# GNSS_A.net
KiCad netlist of a schematic drawn in Altium Designer
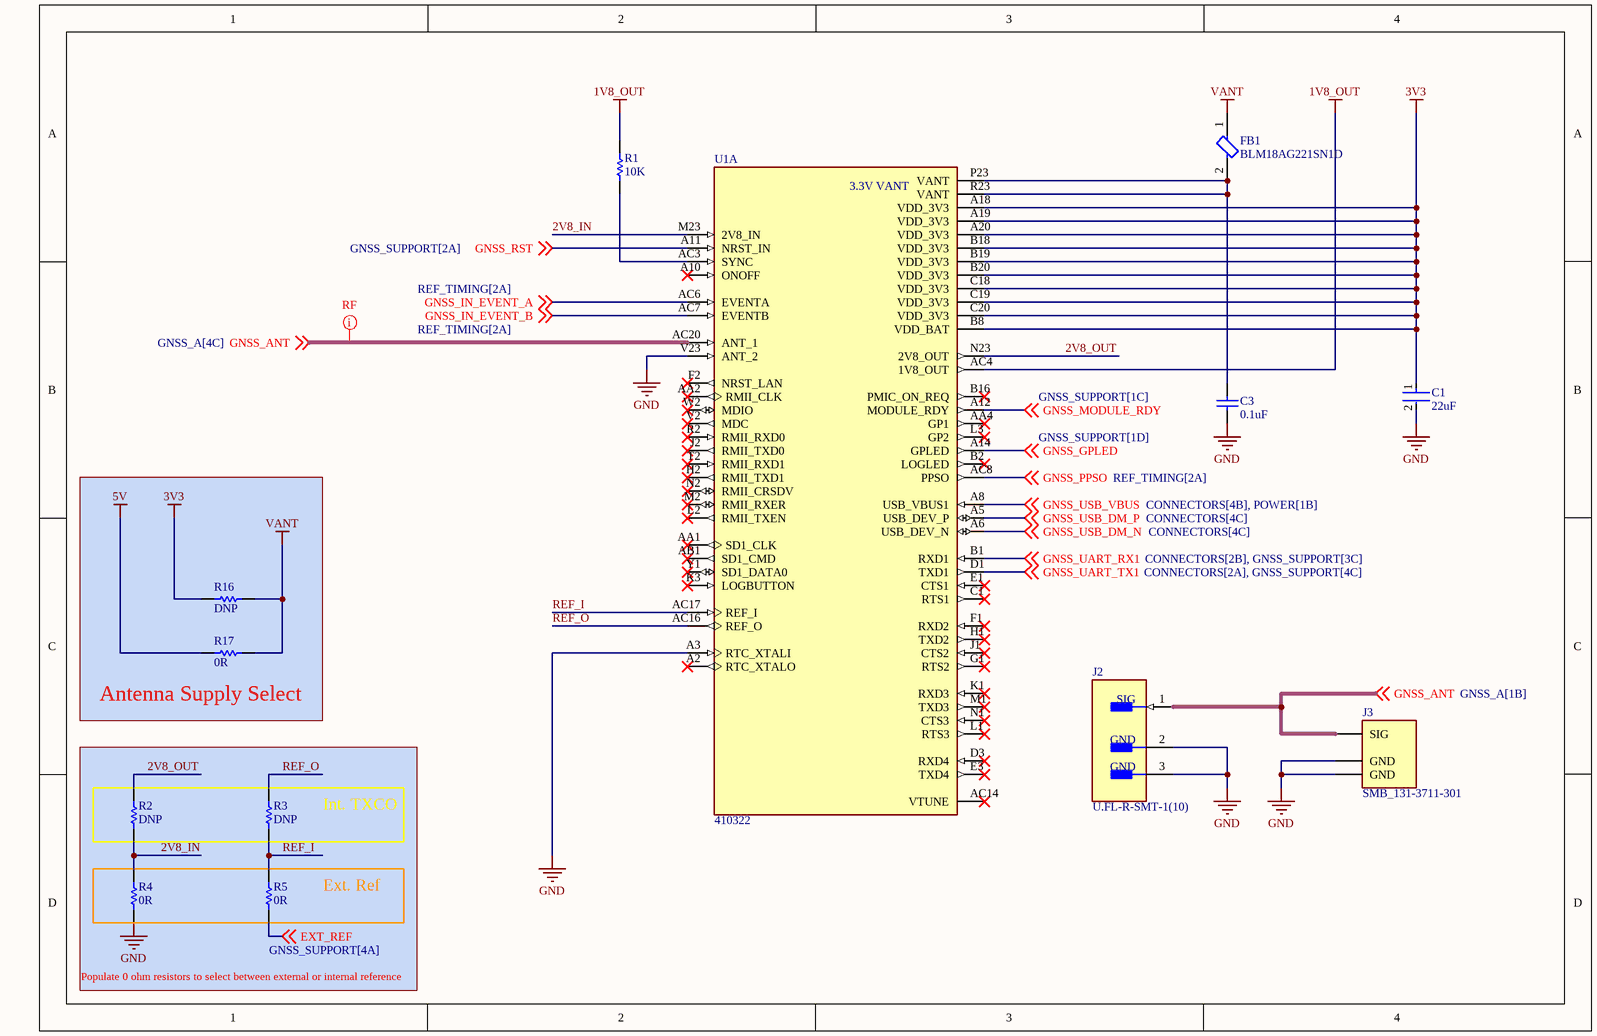
[diagram p0: GNSS_A.SchDoc]

(export (version "E")
  (design (tool "Eeschema 10.0.6"))
  (components
    (comp (ref "C1")
      (value "22uF")
      (footprint "FP-CL10-IPC_B")
      (description "Cap Ceramic 22uF 10V X5R ±20% Pad SMD 0603 +85°C T/R")
      (fields (field (name "TOLERANCE") "20%"))
      (libsource (lib "Altium Content Vault") (part "b4654b650e69147ec39a6b967a45e02"))
    )
    (comp (ref "C3")
      (value "0.1uF")
      (footprint "CAPC1005X56X25LL10T15")
      (fields
        (field (name "MANUFACTURER") "AVX Interconnect / Elco")
        (field (name "PART NUMBER") "04026D104KAT2A")
      )
      (libsource (lib "Altium Content Vault") (part "CAP"))
    )
    (comp (ref "FB1")
      (value "BLM18AG221SN1D")
      (footprint "FP-BLM18-0_15-t0_8-IPC_A")
      (description "Chip Ferrite Bead, 0603, 220Ω @ 100MHz, 0.25Ω, 25%, 700mA")
      (fields (field (name "TOLERANCE") "25%"))
      (libsource (lib "Altium Content Vault") (part "5f30dd21d616792df468990f7003faa"))
    )
    (comp (ref "J2")
      (value "U.FL-R-SMT-1(10)")
      (footprint "FP-U_FL-R-SMT-1_10-MFG")
      (description "CONN U.FL RCPT STR 50 OHM SMD")
      (libsource (lib "Altium Content Vault") (part "7158abf7d987fa84906f6fb0d115710"))
    )
    (comp (ref "J3")
      (value "SMB_131-3711-301")
      (footprint "SMB_131-3711-301")
      (description "Rf Coaxial Board Mount Connector")
      (fields
        (field (name "MANUFACTURER") "Bel Cinch")
        (field (name "MANUFACTURER PART NUMBER") "131-3711-301")
      )
      (libsource (lib "GNSS_Receiver_Library") (part "SMB_131-3711-301"))
    )
    (comp (ref "R1")
      (value "10K")
      (footprint "RESC1005X40X25LL05T10")
      (fields (field (name "PART NUMBER") "RC0402FR-0710KL") (field (name "MANUFACTURER") "Yageo / Phycomp"))
      (libsource (lib "Altium Content Vault") (part "RES"))
    )
    (comp (ref "R2")
      (value "DNP")
      (footprint "RESC1005X40X25NL05T10")
      (fields (field (name "MANUFACTURER") "Yageo / Phycomp") (field (name "PART NUMBER") "RC0402JR-070RL"))
      (libsource (lib "Altium Content Vault") (part "RES"))
    )
    (comp (ref "R3")
      (value "DNP")
      (footprint "RESC1005X40X25NL05T10")
      (fields (field (name "MANUFACTURER") "Yageo / Phycomp") (field (name "PART NUMBER") "RC0402JR-070RL"))
      (libsource (lib "Altium Content Vault") (part "RES"))
    )
    (comp (ref "R4")
      (value "0R")
      (footprint "RESC1005X40X25NL05T10")
      (fields (field (name "MANUFACTURER") "Yageo / Phycomp") (field (name "PART NUMBER") "RC0402JR-070RL"))
      (libsource (lib "Altium Content Vault") (part "RES"))
    )
    (comp (ref "R5")
      (value "0R")
      (footprint "RESC1005X40X25NL05T10")
      (fields (field (name "MANUFACTURER") "Yageo / Phycomp") (field (name "PART NUMBER") "RC0402JR-070RL"))
      (libsource (lib "Altium Content Vault") (part "RES"))
    )
    (comp (ref "R16")
      (value "DNP")
      (footprint "RESC1005X40X25NL05T10")
      (fields (field (name "MANUFACTURER") "Yageo / Phycomp") (field (name "PART NUMBER") "RC0402JR-070RL"))
      (libsource (lib "Altium Content Vault") (part "RES"))
    )
    (comp (ref "R17")
      (value "0R")
      (footprint "RESC1005X40X25NL05T10")
      (fields (field (name "MANUFACTURER") "Yageo / Phycomp") (field (name "PART NUMBER") "RC0402JR-070RL"))
      (libsource (lib "Altium Content Vault") (part "RES"))
    )
    (comp (ref "U1")
      (value "410322")
      (footprint "LGA239C127P23X23_3100X3100X417N")
      (description "mosaicâ„¢-X5 RF Receiver BeiDou, Galileo, GLONASS, GNSS, GPS")
      (fields (field (name "MF") "Septentrio Inc."))
      (libsource (lib "410322") (part "410322"))
    )
  )
  (nets
    (net (code "1") (name "/2V8_IN") (class "Default")
      (node (ref "R2") (pin "2") (pinfunction "2_2") (pintype "passive"))
      (node (ref "R4") (pin "1") (pinfunction "1_1") (pintype "passive"))
      (node (ref "U1") (pin "M23") (pinfunction "2V8_IN_M23") (pintype "input"))
    )
    (net (code "2") (name "/2V8_OUT") (class "Default")
      (node (ref "R2") (pin "1") (pinfunction "1_1") (pintype "passive"))
      (node (ref "U1") (pin "N23") (pinfunction "2V8_OUT_N23") (pintype "output"))
    )
    (net (code "3") (name "/REF_I") (class "Default")
      (node (ref "R3") (pin "2") (pinfunction "2_2") (pintype "passive"))
      (node (ref "R5") (pin "1") (pinfunction "1_1") (pintype "passive"))
      (node (ref "U1") (pin "AC17") (pinfunction "REF_I_AC17") (pintype "input"))
    )
    (net (code "4") (name "/REF_O") (class "Default")
      (node (ref "R3") (pin "1") (pinfunction "1_1") (pintype "passive"))
      (node (ref "U1") (pin "AC16") (pinfunction "REF_O_AC16") (pintype "output"))
    )
    (net (code "5") (name "1V8_OUT") (class "Default")
      (node (ref "R1") (pin "2") (pinfunction "2_2") (pintype "passive"))
      (node (ref "U1") (pin "AC4") (pinfunction "1V8_OUT_AC4") (pintype "output"))
    )
    (net (code "6") (name "3V3") (class "Default")
      (node (ref "C1") (pin "1") (pinfunction "1_1") (pintype "passive"))
      (node (ref "R16") (pin "1") (pinfunction "1_1") (pintype "passive"))
      (node (ref "U1") (pin "A18") (pinfunction "VDD_3V3_A18") (pintype "power_in"))
      (node (ref "U1") (pin "A19") (pinfunction "VDD_3V3_A19") (pintype "power_in"))
      (node (ref "U1") (pin "A20") (pinfunction "VDD_3V3_A20") (pintype "power_in"))
      (node (ref "U1") (pin "B18") (pinfunction "VDD_3V3_B18") (pintype "power_in"))
      (node (ref "U1") (pin "B19") (pinfunction "VDD_3V3_B19") (pintype "power_in"))
      (node (ref "U1") (pin "B20") (pinfunction "VDD_3V3_B20") (pintype "power_in"))
      (node (ref "U1") (pin "B8") (pinfunction "VDD_BAT_B8") (pintype "power_in"))
      (node (ref "U1") (pin "C18") (pinfunction "VDD_3V3_C18") (pintype "power_in"))
      (node (ref "U1") (pin "C19") (pinfunction "VDD_3V3_C19") (pintype "power_in"))
      (node (ref "U1") (pin "C20") (pinfunction "VDD_3V3_C20") (pintype "power_in"))
    )
    (net (code "7") (name "5V") (class "Default")
      (node (ref "R17") (pin "1") (pinfunction "1_1") (pintype "passive"))
    )
    (net (code "8") (name "EXT_REF") (class "Default")
      (node (ref "R5") (pin "2") (pinfunction "2_2") (pintype "passive"))
    )
    (net (code "9") (name "GND") (class "Default")
      (node (ref "C1") (pin "2") (pinfunction "2_2") (pintype "passive"))
      (node (ref "C3") (pin "1") (pinfunction "1_1") (pintype "passive"))
      (node (ref "J2") (pin "2") (pinfunction "GND_2") (pintype "power_in"))
      (node (ref "J2") (pin "3") (pinfunction "GND_3") (pintype "power_in"))
      (node (ref "J3") (pin "2") (pinfunction "GND_2") (pintype "passive"))
      (node (ref "J3") (pin "3") (pinfunction "GND_3") (pintype "passive"))
      (node (ref "R4") (pin "2") (pinfunction "2_2") (pintype "passive"))
      (node (ref "U1") (pin "A3") (pinfunction "RTC_XTALI_A3") (pintype "input"))
      (node (ref "U1") (pin "V23") (pinfunction "ANT_2_V23") (pintype "input"))
    )
    (net (code "10") (name "GNSS_ANT") (class "Default")
      (node (ref "J2") (pin "1") (pinfunction "SIG_1") (pintype "input"))
      (node (ref "J3") (pin "1") (pinfunction "SIG_1") (pintype "passive"))
      (node (ref "U1") (pin "AC20") (pinfunction "ANT_1_AC20") (pintype "input"))
    )
    (net (code "11") (name "GNSS_GPLED") (class "Default")
      (node (ref "U1") (pin "A14") (pinfunction "GPLED_A14") (pintype "output"))
    )
    (net (code "12") (name "GNSS_IN_EVENT_A") (class "Default")
      (node (ref "U1") (pin "AC6") (pinfunction "EVENTA_AC6") (pintype "input"))
    )
    (net (code "13") (name "GNSS_IN_EVENT_B") (class "Default")
      (node (ref "U1") (pin "AC7") (pinfunction "EVENTB_AC7") (pintype "input"))
    )
    (net (code "14") (name "GNSS_MODULE_RDY") (class "Default")
      (node (ref "U1") (pin "A12") (pinfunction "MODULE_RDY_A12") (pintype "output"))
    )
    (net (code "15") (name "GNSS_PPSO") (class "Default")
      (node (ref "U1") (pin "AC8") (pinfunction "PPSO_AC8") (pintype "output"))
    )
    (net (code "16") (name "GNSS_RST") (class "Default")
      (node (ref "U1") (pin "A11") (pinfunction "NRST_IN_A11") (pintype "input"))
    )
    (net (code "17") (name "GNSS_UART_RX1") (class "Default")
      (node (ref "U1") (pin "B1") (pinfunction "RXD1_B1") (pintype "input"))
    )
    (net (code "18") (name "GNSS_UART_TX1") (class "Default")
      (node (ref "U1") (pin "D1") (pinfunction "TXD1_D1") (pintype "output"))
    )
    (net (code "19") (name "GNSS_USB_DM_N") (class "Default")
      (node (ref "U1") (pin "A6") (pinfunction "USB_DEV_N_A6") (pintype "bidirectional"))
    )
    (net (code "20") (name "GNSS_USB_DM_P") (class "Default")
      (node (ref "U1") (pin "A5") (pinfunction "USB_DEV_P_A5") (pintype "bidirectional"))
    )
    (net (code "21") (name "GNSS_USB_VBUS") (class "Default")
      (node (ref "U1") (pin "A8") (pinfunction "USB_VBUS1_A8") (pintype "input"))
    )
    (net (code "22") (name "Net-(C3-Pad2)") (class "Default")
      (node (ref "C3") (pin "2") (pinfunction "2_2") (pintype "passive"))
      (node (ref "FB1") (pin "2") (pinfunction "2_2") (pintype "passive"))
      (node (ref "U1") (pin "P23") (pinfunction "VANT_P23") (pintype "power_in"))
      (node (ref "U1") (pin "R23") (pinfunction "VANT_R23") (pintype "power_in"))
    )
    (net (code "23") (name "Net-(U1A-SYNC)") (class "Default")
      (node (ref "R1") (pin "1") (pinfunction "1_1") (pintype "passive"))
      (node (ref "U1") (pin "AC3") (pinfunction "SYNC_AC3") (pintype "input"))
    )
    (net (code "24") (name "VANT") (class "Default")
      (node (ref "FB1") (pin "1") (pinfunction "1_1") (pintype "passive"))
      (node (ref "R16") (pin "2") (pinfunction "2_2") (pintype "passive"))
      (node (ref "R17") (pin "2") (pinfunction "2_2") (pintype "passive"))
    )
    (net (code "25") (name "unconnected-(U1A-CTS1-PadE1)") (class "Default")
      (node (ref "U1") (pin "E1") (pinfunction "CTS1_E1") (pintype "input+no_connect"))
    )
    (net (code "26") (name "unconnected-(U1A-CTS2-PadJ1)") (class "Default")
      (node (ref "U1") (pin "J1") (pinfunction "CTS2_J1") (pintype "input+no_connect"))
    )
    (net (code "27") (name "unconnected-(U1A-CTS3-PadN1)") (class "Default")
      (node (ref "U1") (pin "N1") (pinfunction "CTS3_N1") (pintype "input+no_connect"))
    )
    (net (code "28") (name "unconnected-(U1A-GP1-PadAA4)") (class "Default")
      (node (ref "U1") (pin "AA4") (pinfunction "GP1_AA4") (pintype "output+no_connect"))
    )
    (net (code "29") (name "unconnected-(U1A-GP2-PadL3)") (class "Default")
      (node (ref "U1") (pin "L3") (pinfunction "GP2_L3") (pintype "output+no_connect"))
    )
    (net (code "30") (name "unconnected-(U1A-LOGBUTTON-PadK3)") (class "Default")
      (node (ref "U1") (pin "K3") (pinfunction "LOGBUTTON_K3") (pintype "input+no_connect"))
    )
    (net (code "31") (name "unconnected-(U1A-LOGLED-PadB2)") (class "Default")
      (node (ref "U1") (pin "B2") (pinfunction "LOGLED_B2") (pintype "output+no_connect"))
    )
    (net (code "32") (name "unconnected-(U1A-MDC-PadV2)") (class "Default")
      (node (ref "U1") (pin "V2") (pinfunction "MDC_V2") (pintype "output+no_connect"))
    )
    (net (code "33") (name "unconnected-(U1A-MDIO-PadW2)") (class "Default")
      (node (ref "U1") (pin "W2") (pinfunction "MDIO_W2") (pintype "bidirectional+no_connect"))
    )
    (net (code "34") (name "unconnected-(U1A-NRST_LAN-PadF2)") (class "Default")
      (node (ref "U1") (pin "F2") (pinfunction "NRST_LAN_F2") (pintype "output+no_connect"))
    )
    (net (code "35") (name "unconnected-(U1A-ONOFF-PadA10)") (class "Default")
      (node (ref "U1") (pin "A10") (pinfunction "ONOFF_A10") (pintype "input+no_connect"))
    )
    (net (code "36") (name "unconnected-(U1A-PMIC_ON_REQ-PadB16)") (class "Default")
      (node (ref "U1") (pin "B16") (pinfunction "PMIC_ON_REQ_B16") (pintype "output+no_connect"))
    )
    (net (code "37") (name "unconnected-(U1A-RMII_CLK-PadAA2)") (class "Default")
      (node (ref "U1") (pin "AA2") (pinfunction "RMII_CLK_AA2") (pintype "output+no_connect"))
    )
    (net (code "38") (name "unconnected-(U1A-RMII_CRSDV-PadN2)") (class "Default")
      (node (ref "U1") (pin "N2") (pinfunction "RMII_CRSDV_N2") (pintype "bidirectional+no_connect"))
    )
    (net (code "39") (name "unconnected-(U1A-RMII_RXD0-PadR2)") (class "Default")
      (node (ref "U1") (pin "R2") (pinfunction "RMII_RXD0_R2") (pintype "input+no_connect"))
    )
    (net (code "40") (name "unconnected-(U1A-RMII_RXD1-PadT2)") (class "Default")
      (node (ref "U1") (pin "T2") (pinfunction "RMII_RXD1_T2") (pintype "input+no_connect"))
    )
    (net (code "41") (name "unconnected-(U1A-RMII_RXER-PadM2)") (class "Default")
      (node (ref "U1") (pin "M2") (pinfunction "RMII_RXER_M2") (pintype "bidirectional+no_connect"))
    )
    (net (code "42") (name "unconnected-(U1A-RMII_TXD0-PadJ2)") (class "Default")
      (node (ref "U1") (pin "J2") (pinfunction "RMII_TXD0_J2") (pintype "output+no_connect"))
    )
    (net (code "43") (name "unconnected-(U1A-RMII_TXD1-PadH2)") (class "Default")
      (node (ref "U1") (pin "H2") (pinfunction "RMII_TXD1_H2") (pintype "output+no_connect"))
    )
    (net (code "44") (name "unconnected-(U1A-RMII_TXEN-PadL2)") (class "Default")
      (node (ref "U1") (pin "L2") (pinfunction "RMII_TXEN_L2") (pintype "output+no_connect"))
    )
    (net (code "45") (name "unconnected-(U1A-RTC_XTALO-PadA2)") (class "Default")
      (node (ref "U1") (pin "A2") (pinfunction "RTC_XTALO_A2") (pintype "output+no_connect"))
    )
    (net (code "46") (name "unconnected-(U1A-RTS1-PadC1)") (class "Default")
      (node (ref "U1") (pin "C1") (pinfunction "RTS1_C1") (pintype "output+no_connect"))
    )
    (net (code "47") (name "unconnected-(U1A-RTS2-PadG1)") (class "Default")
      (node (ref "U1") (pin "G1") (pinfunction "RTS2_G1") (pintype "output+no_connect"))
    )
    (net (code "48") (name "unconnected-(U1A-RTS3-PadL1)") (class "Default")
      (node (ref "U1") (pin "L1") (pinfunction "RTS3_L1") (pintype "output+no_connect"))
    )
    (net (code "49") (name "unconnected-(U1A-RXD2-PadF1)") (class "Default")
      (node (ref "U1") (pin "F1") (pinfunction "RXD2_F1") (pintype "input+no_connect"))
    )
    (net (code "50") (name "unconnected-(U1A-RXD3-PadK1)") (class "Default")
      (node (ref "U1") (pin "K1") (pinfunction "RXD3_K1") (pintype "input+no_connect"))
    )
    (net (code "51") (name "unconnected-(U1A-RXD4-PadD3)") (class "Default")
      (node (ref "U1") (pin "D3") (pinfunction "RXD4_D3") (pintype "input+no_connect"))
    )
    (net (code "52") (name "unconnected-(U1A-SD1_CLK-PadAA1)") (class "Default")
      (node (ref "U1") (pin "AA1") (pinfunction "SD1_CLK_AA1") (pintype "output+no_connect"))
    )
    (net (code "53") (name "unconnected-(U1A-SD1_CMD-PadAB1)") (class "Default")
      (node (ref "U1") (pin "AB1") (pinfunction "SD1_CMD_AB1") (pintype "output+no_connect"))
    )
    (net (code "54") (name "unconnected-(U1A-SD1_DATA0-PadY1)") (class "Default")
      (node (ref "U1") (pin "Y1") (pinfunction "SD1_DATA0_Y1") (pintype "bidirectional+no_connect"))
    )
    (net (code "55") (name "unconnected-(U1A-TXD2-PadH1)") (class "Default")
      (node (ref "U1") (pin "H1") (pinfunction "TXD2_H1") (pintype "output+no_connect"))
    )
    (net (code "56") (name "unconnected-(U1A-TXD3-PadM1)") (class "Default")
      (node (ref "U1") (pin "M1") (pinfunction "TXD3_M1") (pintype "output+no_connect"))
    )
    (net (code "57") (name "unconnected-(U1A-TXD4-PadE3)") (class "Default")
      (node (ref "U1") (pin "E3") (pinfunction "TXD4_E3") (pintype "output+no_connect"))
    )
    (net (code "58") (name "unconnected-(U1A-VTUNE-PadAC14)") (class "Default")
      (node (ref "U1") (pin "AC14") (pinfunction "VTUNE_AC14") (pintype "passive+no_connect"))
    )
  )
)
